# hw-demo01.net
KiCad netlist of a schematic drawn in EAGLE
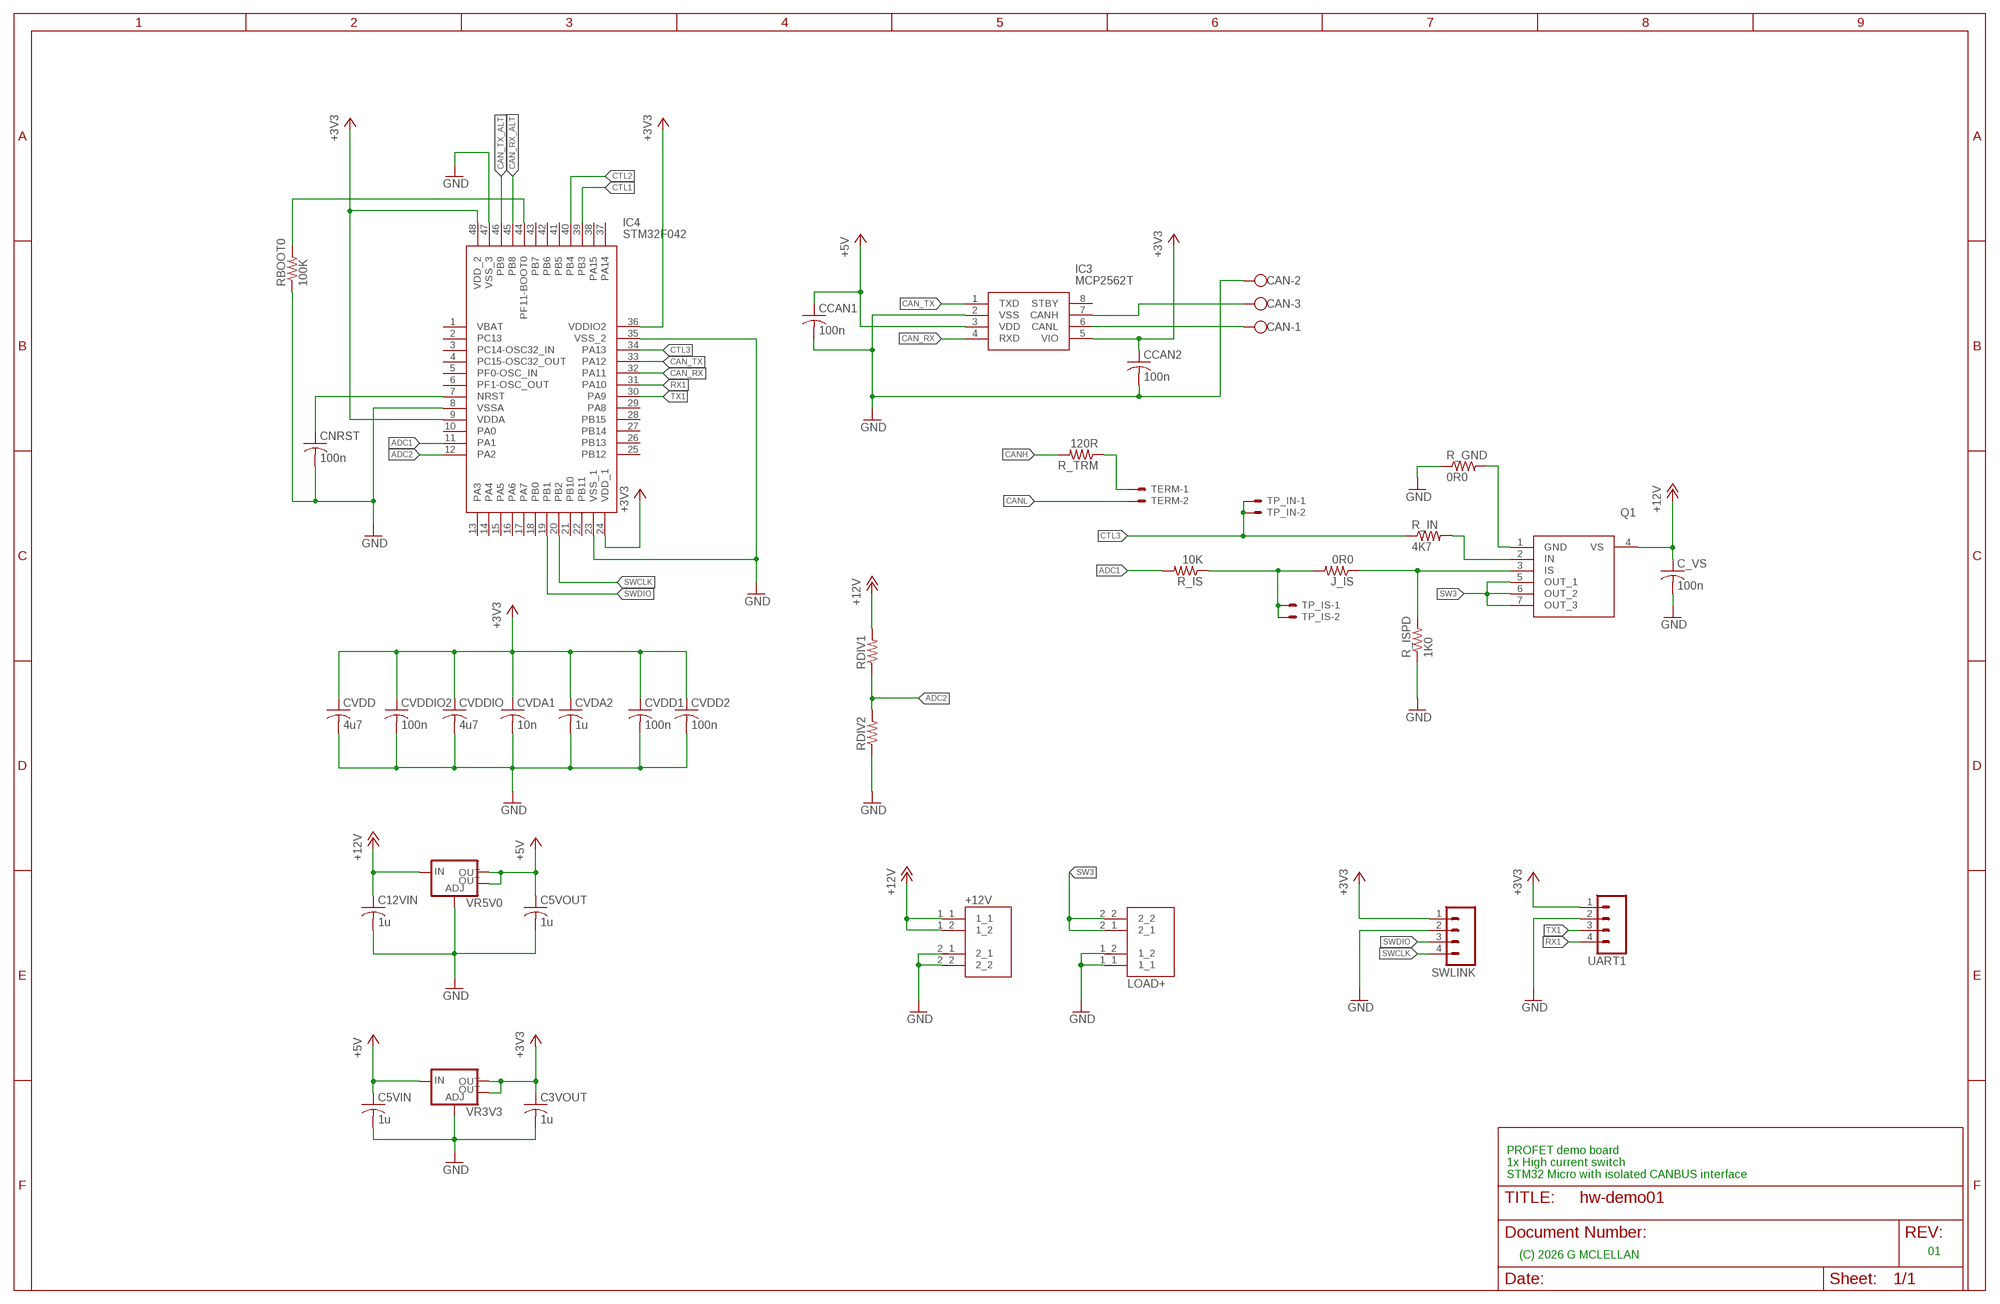
[diagram p0: schematic, sheet 1]

(export (version "E")
  (design (tool "Eeschema 10.0.6"))
  (components
    (comp (ref "+12V")
      (value "VP0265840000G")
      (footprint "eagle-import:AMPHENOL_VP0265840000G")
      (fields (field (name "MANUFACTURER") "Amphenol Anytek"))
      (libsource (lib "eagle-import") (part "VP0265840000G"))
    )
    (comp (ref "C3VOUT")
      (value "1u")
      (footprint "eagle-import:C0805K")
      (libsource (lib "eagle-import") (part "C-USC0805K"))
    )
    (comp (ref "C5VIN")
      (value "1u")
      (footprint "eagle-import:C1206K")
      (libsource (lib "eagle-import") (part "C-USC1206K"))
    )
    (comp (ref "C5VOUT")
      (value "1u")
      (footprint "eagle-import:C0805K")
      (libsource (lib "eagle-import") (part "C-USC0805K"))
    )
    (comp (ref "C12VIN")
      (value "1u")
      (footprint "eagle-import:C1206K")
      (libsource (lib "eagle-import") (part "C-USC1206K"))
    )
    (comp (ref "CAN")
      (value "W237-103")
      (footprint "eagle-import:W237-103")
      (fields (field (name "MPN") "237-103"))
      (libsource (lib "eagle-import") (part "W237-103"))
    )
    (comp (ref "CCAN1")
      (value "100n")
      (footprint "eagle-import:C0603K")
      (libsource (lib "eagle-import") (part "C-USC0603K"))
    )
    (comp (ref "CCAN2")
      (value "100n")
      (footprint "eagle-import:C0603K")
      (libsource (lib "eagle-import") (part "C-USC0603K"))
    )
    (comp (ref "CNRST")
      (value "100n")
      (footprint "eagle-import:C0603K")
      (libsource (lib "eagle-import") (part "C-USC0603K"))
    )
    (comp (ref "CVDA1")
      (value "10n")
      (footprint "eagle-import:C0603K")
      (libsource (lib "eagle-import") (part "C-USC0603K"))
    )
    (comp (ref "CVDA2")
      (value "1u")
      (footprint "eagle-import:C0603K")
      (libsource (lib "eagle-import") (part "C-USC0603K"))
    )
    (comp (ref "CVDD")
      (value "4u7")
      (footprint "eagle-import:C0603K")
      (libsource (lib "eagle-import") (part "C-USC0603K"))
    )
    (comp (ref "CVDD1")
      (value "100n")
      (footprint "eagle-import:C0603K")
      (libsource (lib "eagle-import") (part "C-USC0603K"))
    )
    (comp (ref "CVDD2")
      (value "100n")
      (footprint "eagle-import:C0603K")
      (libsource (lib "eagle-import") (part "C-USC0603K"))
    )
    (comp (ref "CVDDIO")
      (value "4u7")
      (footprint "eagle-import:C0603K")
      (libsource (lib "eagle-import") (part "C-USC0603K"))
    )
    (comp (ref "CVDDIO2")
      (value "100n")
      (footprint "eagle-import:C0603K")
      (libsource (lib "eagle-import") (part "C-USC0603K"))
    )
    (comp (ref "C_VS")
      (value "100n")
      (footprint "eagle-import:C0603K")
      (libsource (lib "eagle-import") (part "C-USC0603K"))
    )
    (comp (ref "IC3")
      (value "MCP2562T")
      (footprint "eagle-import:SOIC127P600X175-8N")
      (fields
        (field (name "MANUFACTURER_PART_NUMBER") "MCP2562T-H/SN")
        (field (name "MOUSER_PART_NUMBER") "579-MCP2562T-H/SN")
      )
      (libsource (lib "eagle-import") (part "MCP2562T-H_SN"))
    )
    (comp (ref "IC4")
      (value "STM32F042")
      (footprint "eagle-import:QFP50P900X900X160-48N")
      (fields
        (field (name "MANUFACTURER_PART_NUMBER") "STM32F042C6T7")
        (field (name "MOUSER_PART_NUMBER") "511-STM32F042C6T7")
      )
      (libsource (lib "eagle-import") (part "STM32F042C6T7"))
    )
    (comp (ref "J_IS")
      (value "0R0")
      (footprint "eagle-import:0207_12")
      (libsource (lib "eagle-import") (part "R-US_0207/12"))
    )
    (comp (ref "LOAD+")
      (value "VP0265840000G")
      (footprint "eagle-import:AMPHENOL_VP0265840000G")
      (fields (field (name "MANUFACTURER") "Amphenol Anytek"))
      (libsource (lib "eagle-import") (part "VP0265840000G"))
    )
    (comp (ref "Q1")
      (value "BTS500101TADATMA2")
      (footprint "eagle-import:BTS500101TADATMA2")
      (fields (field (name "MOUSER_PART_NUMBER") "726-BTS500101TADATM2"))
      (libsource (lib "eagle-import") (part "BTS500101TADATMA2"))
    )
    (comp (ref "RBOOT0")
      (value "100K")
      (footprint "eagle-import:R0603")
      (libsource (lib "eagle-import") (part "R-US_R0603"))
    )
    (comp (ref "RDIV1")
      (value "R-US_R0805")
      (footprint "eagle-import:R0805")
      (libsource (lib "eagle-import") (part "R-US_R0805"))
    )
    (comp (ref "RDIV2")
      (value "R-US_R0805")
      (footprint "eagle-import:R0805")
      (libsource (lib "eagle-import") (part "R-US_R0805"))
    )
    (comp (ref "R_GND")
      (value "0R0")
      (footprint "eagle-import:R1206W")
      (libsource (lib "eagle-import") (part "R-US_R1206W"))
    )
    (comp (ref "R_IN")
      (value "4K7")
      (footprint "eagle-import:0207_12")
      (libsource (lib "eagle-import") (part "R-US_0207/12"))
    )
    (comp (ref "R_IS")
      (value "10K")
      (footprint "eagle-import:0207_12")
      (libsource (lib "eagle-import") (part "R-US_0207/12"))
    )
    (comp (ref "R_ISPD")
      (value "1K0")
      (footprint "eagle-import:0207_12")
      (libsource (lib "eagle-import") (part "R-US_0207/12"))
    )
    (comp (ref "R_TRM")
      (value "120R")
      (footprint "eagle-import:0204_7")
      (libsource (lib "eagle-import") (part "R-US_0204/7"))
    )
    (comp (ref "SWLINK")
      (value "M04LOCK")
      (footprint "eagle-import:1X04_LOCK")
      (libsource (lib "eagle-import") (part "M04LOCK"))
    )
    (comp (ref "TERM")
      (value "22-23-2021")
      (footprint "eagle-import:22-23-2021")
      (fields (field (name "MF") "MOLEX"))
      (libsource (lib "eagle-import") (part "22-23-2021"))
    )
    (comp (ref "TP_IN")
      (value "22-23-2021")
      (footprint "eagle-import:22-23-2021")
      (fields (field (name "MF") "MOLEX"))
      (libsource (lib "eagle-import") (part "22-23-2021"))
    )
    (comp (ref "TP_IS")
      (value "22-23-2021")
      (footprint "eagle-import:22-23-2021")
      (fields (field (name "MF") "MOLEX"))
      (libsource (lib "eagle-import") (part "22-23-2021"))
    )
    (comp (ref "UART1")
      (value "M04LOCK")
      (footprint "eagle-import:1X04_LOCK")
      (libsource (lib "eagle-import") (part "M04LOCK"))
    )
    (comp (ref "VR3V3")
      (value "V_REG_LM1117SOT223")
      (footprint "eagle-import:SOT223")
      (libsource (lib "eagle-import") (part "V_REG_LM1117SOT223"))
    )
    (comp (ref "VR5V0")
      (value "V_REG_LM1117SOT223")
      (footprint "eagle-import:SOT223")
      (libsource (lib "eagle-import") (part "V_REG_LM1117SOT223"))
    )
  )
  (nets
    (net (code "1") (name "+3V3") (class "Default")
      (node (ref "C3VOUT") (pin "1") (pinfunction "1_1") (pintype "passive"))
      (node (ref "CCAN2") (pin "1") (pinfunction "1_1") (pintype "passive"))
      (node (ref "CVDA1") (pin "1") (pinfunction "1_1") (pintype "passive"))
      (node (ref "CVDA2") (pin "1") (pinfunction "1_1") (pintype "passive"))
      (node (ref "CVDD") (pin "1") (pinfunction "1_1") (pintype "passive"))
      (node (ref "CVDD1") (pin "1") (pinfunction "1_1") (pintype "passive"))
      (node (ref "CVDD2") (pin "1") (pinfunction "1_1") (pintype "passive"))
      (node (ref "CVDDIO") (pin "1") (pinfunction "1_1") (pintype "passive"))
      (node (ref "CVDDIO2") (pin "1") (pinfunction "1_1") (pintype "passive"))
      (node (ref "IC3") (pin "5") (pinfunction "VIO_5") (pintype "bidirectional"))
      (node (ref "IC4") (pin "24") (pinfunction "VDD_1_24") (pintype "bidirectional"))
      (node (ref "IC4") (pin "36") (pinfunction "VDDIO2_36") (pintype "bidirectional"))
      (node (ref "IC4") (pin "48") (pinfunction "VDD_2_48") (pintype "bidirectional"))
      (node (ref "IC4") (pin "9") (pinfunction "VDDA_9") (pintype "bidirectional"))
      (node (ref "SWLINK") (pin "1") (pinfunction "1_1") (pintype "passive"))
      (node (ref "UART1") (pin "1") (pinfunction "1_1") (pintype "passive"))
      (node (ref "VR3V3") (pin "2") (pinfunction "OUT_2") (pintype "output"))
      (node (ref "VR3V3") (pin "4") (pinfunction "OUT_4") (pintype "output"))
    )
    (net (code "2") (name "+5V") (class "Default")
      (node (ref "C5VIN") (pin "1") (pinfunction "1_1") (pintype "passive"))
      (node (ref "C5VOUT") (pin "1") (pinfunction "1_1") (pintype "passive"))
      (node (ref "CCAN1") (pin "1") (pinfunction "1_1") (pintype "passive"))
      (node (ref "IC3") (pin "3") (pinfunction "VDD_3") (pintype "bidirectional"))
      (node (ref "VR3V3") (pin "3") (pinfunction "IN_3") (pintype "input"))
      (node (ref "VR5V0") (pin "2") (pinfunction "OUT_2") (pintype "output"))
      (node (ref "VR5V0") (pin "4") (pinfunction "OUT_4") (pintype "output"))
    )
    (net (code "3") (name "+12V") (class "Default")
      (node (ref "+12V") (pin "1_1") (pinfunction "1_1_1_1") (pintype "passive"))
      (node (ref "+12V") (pin "1_2") (pinfunction "1_2_1_2") (pintype "passive"))
      (node (ref "C12VIN") (pin "1") (pinfunction "1_1") (pintype "passive"))
      (node (ref "C_VS") (pin "1") (pinfunction "1_1") (pintype "passive"))
      (node (ref "Q1") (pin "4") (pinfunction "VS_4") (pintype "bidirectional"))
      (node (ref "RDIV1") (pin "2") (pinfunction "2_2") (pintype "passive"))
      (node (ref "VR5V0") (pin "3") (pinfunction "IN_3") (pintype "input"))
    )
    (net (code "4") (name "ADC1") (class "Default")
      (node (ref "IC4") (pin "11") (pinfunction "PA1_11") (pintype "bidirectional"))
      (node (ref "R_IS") (pin "2") (pinfunction "2_2") (pintype "passive"))
    )
    (net (code "5") (name "ADC2") (class "Default")
      (node (ref "IC4") (pin "12") (pinfunction "PA2_12") (pintype "bidirectional"))
      (node (ref "RDIV1") (pin "1") (pinfunction "1_1") (pintype "passive"))
      (node (ref "RDIV2") (pin "2") (pinfunction "2_2") (pintype "passive"))
    )
    (net (code "6") (name "CANH") (class "Default")
      (node (ref "CAN") (pin "3") (pinfunction "KL_3") (pintype "passive"))
      (node (ref "IC3") (pin "7") (pinfunction "CANH_7") (pintype "bidirectional"))
      (node (ref "R_TRM") (pin "2") (pinfunction "2_2") (pintype "passive"))
    )
    (net (code "7") (name "CANL") (class "Default")
      (node (ref "CAN") (pin "1") (pinfunction "KL_1") (pintype "passive"))
      (node (ref "IC3") (pin "6") (pinfunction "CANL_6") (pintype "bidirectional"))
      (node (ref "TERM") (pin "2") (pinfunction "S_2") (pintype "passive"))
    )
    (net (code "8") (name "CAN_RX") (class "Default")
      (node (ref "IC3") (pin "4") (pinfunction "RXD_4") (pintype "bidirectional"))
      (node (ref "IC4") (pin "32") (pinfunction "PA11_32") (pintype "bidirectional"))
    )
    (net (code "9") (name "CAN_RX_ALT") (class "Default")
      (node (ref "IC4") (pin "45") (pinfunction "PB8_45") (pintype "bidirectional"))
    )
    (net (code "10") (name "CAN_TX") (class "Default")
      (node (ref "IC3") (pin "1") (pinfunction "TXD_1") (pintype "bidirectional"))
      (node (ref "IC4") (pin "33") (pinfunction "PA12_33") (pintype "bidirectional"))
    )
    (net (code "11") (name "CAN_TX_ALT") (class "Default")
      (node (ref "IC4") (pin "46") (pinfunction "PB9_46") (pintype "bidirectional"))
    )
    (net (code "12") (name "CTL1") (class "Default")
      (node (ref "IC4") (pin "39") (pinfunction "PB3_39") (pintype "bidirectional"))
    )
    (net (code "13") (name "CTL2") (class "Default")
      (node (ref "IC4") (pin "40") (pinfunction "PB4_40") (pintype "bidirectional"))
    )
    (net (code "14") (name "CTL3") (class "Default")
      (node (ref "IC4") (pin "34") (pinfunction "PA13_34") (pintype "bidirectional"))
      (node (ref "R_IN") (pin "1") (pinfunction "1_1") (pintype "passive"))
      (node (ref "TP_IN") (pin "1") (pinfunction "S_1") (pintype "passive"))
      (node (ref "TP_IN") (pin "2") (pinfunction "S_2") (pintype "passive"))
    )
    (net (code "15") (name "GND") (class "Default")
      (node (ref "+12V") (pin "2_1") (pinfunction "2_1_2_1") (pintype "passive"))
      (node (ref "+12V") (pin "2_2") (pinfunction "2_2_2_2") (pintype "passive"))
      (node (ref "C12VIN") (pin "2") (pinfunction "2_2") (pintype "passive"))
      (node (ref "C3VOUT") (pin "2") (pinfunction "2_2") (pintype "passive"))
      (node (ref "C5VIN") (pin "2") (pinfunction "2_2") (pintype "passive"))
      (node (ref "C5VOUT") (pin "2") (pinfunction "2_2") (pintype "passive"))
      (node (ref "CAN") (pin "2") (pinfunction "KL_2") (pintype "passive"))
      (node (ref "CCAN1") (pin "2") (pinfunction "2_2") (pintype "passive"))
      (node (ref "CCAN2") (pin "2") (pinfunction "2_2") (pintype "passive"))
      (node (ref "CNRST") (pin "2") (pinfunction "2_2") (pintype "passive"))
      (node (ref "CVDA1") (pin "2") (pinfunction "2_2") (pintype "passive"))
      (node (ref "CVDA2") (pin "2") (pinfunction "2_2") (pintype "passive"))
      (node (ref "CVDD") (pin "2") (pinfunction "2_2") (pintype "passive"))
      (node (ref "CVDD1") (pin "2") (pinfunction "2_2") (pintype "passive"))
      (node (ref "CVDD2") (pin "2") (pinfunction "2_2") (pintype "passive"))
      (node (ref "CVDDIO") (pin "2") (pinfunction "2_2") (pintype "passive"))
      (node (ref "CVDDIO2") (pin "2") (pinfunction "2_2") (pintype "passive"))
      (node (ref "C_VS") (pin "2") (pinfunction "2_2") (pintype "passive"))
      (node (ref "IC3") (pin "2") (pinfunction "VSS_2") (pintype "bidirectional"))
      (node (ref "IC4") (pin "23") (pinfunction "VSS_1_23") (pintype "bidirectional"))
      (node (ref "IC4") (pin "35") (pinfunction "VSS_2_35") (pintype "bidirectional"))
      (node (ref "IC4") (pin "47") (pinfunction "VSS_3_47") (pintype "bidirectional"))
      (node (ref "IC4") (pin "8") (pinfunction "VSSA_8") (pintype "bidirectional"))
      (node (ref "LOAD+") (pin "1_1") (pinfunction "1_1_1_1") (pintype "passive"))
      (node (ref "LOAD+") (pin "1_2") (pinfunction "1_2_1_2") (pintype "passive"))
      (node (ref "RBOOT0") (pin "1") (pinfunction "1_1") (pintype "passive"))
      (node (ref "RDIV2") (pin "1") (pinfunction "1_1") (pintype "passive"))
      (node (ref "R_GND") (pin "1") (pinfunction "1_1") (pintype "passive"))
      (node (ref "R_ISPD") (pin "1") (pinfunction "1_1") (pintype "passive"))
      (node (ref "SWLINK") (pin "2") (pinfunction "2_2") (pintype "passive"))
      (node (ref "UART1") (pin "2") (pinfunction "2_2") (pintype "passive"))
      (node (ref "VR3V3") (pin "1") (pinfunction "ADJ_1") (pintype "input"))
      (node (ref "VR5V0") (pin "1") (pinfunction "ADJ_1") (pintype "input"))
    )
    (net (code "16") (name "Net-(IC4-NRST)") (class "Default")
      (node (ref "CNRST") (pin "1") (pinfunction "1_1") (pintype "passive"))
      (node (ref "IC4") (pin "7") (pinfunction "NRST_7") (pintype "bidirectional"))
    )
    (net (code "17") (name "Net-(IC4-PF11-BOOT0)") (class "Default")
      (node (ref "IC4") (pin "44") (pinfunction "PF11-BOOT0_44") (pintype "bidirectional"))
      (node (ref "RBOOT0") (pin "2") (pinfunction "2_2") (pintype "passive"))
    )
    (net (code "18") (name "Net-(Q1-GND)") (class "Default")
      (node (ref "Q1") (pin "1") (pinfunction "GND_1") (pintype "bidirectional"))
      (node (ref "R_GND") (pin "2") (pinfunction "2_2") (pintype "passive"))
    )
    (net (code "19") (name "Net-(Q1-IN)") (class "Default")
      (node (ref "Q1") (pin "2") (pinfunction "IN_2") (pintype "bidirectional"))
      (node (ref "R_IN") (pin "2") (pinfunction "2_2") (pintype "passive"))
    )
    (net (code "20") (name "Net-(Q1-IS)") (class "Default")
      (node (ref "J_IS") (pin "1") (pinfunction "1_1") (pintype "passive"))
      (node (ref "Q1") (pin "3") (pinfunction "IS_3") (pintype "bidirectional"))
      (node (ref "R_ISPD") (pin "2") (pinfunction "2_2") (pintype "passive"))
    )
    (net (code "21") (name "Net-(TERMA-S)") (class "Default")
      (node (ref "R_TRM") (pin "1") (pinfunction "1_1") (pintype "passive"))
      (node (ref "TERM") (pin "1") (pinfunction "S_1") (pintype "passive"))
    )
    (net (code "22") (name "Net-(TP_ISA-S)") (class "Default")
      (node (ref "J_IS") (pin "2") (pinfunction "2_2") (pintype "passive"))
      (node (ref "R_IS") (pin "1") (pinfunction "1_1") (pintype "passive"))
      (node (ref "TP_IS") (pin "1") (pinfunction "S_1") (pintype "passive"))
      (node (ref "TP_IS") (pin "2") (pinfunction "S_2") (pintype "passive"))
    )
    (net (code "23") (name "RX1") (class "Default")
      (node (ref "IC4") (pin "31") (pinfunction "PA10_31") (pintype "bidirectional"))
      (node (ref "UART1") (pin "4") (pinfunction "4_4") (pintype "passive"))
    )
    (net (code "24") (name "SW3") (class "Default")
      (node (ref "LOAD+") (pin "2_1") (pinfunction "2_1_2_1") (pintype "passive"))
      (node (ref "LOAD+") (pin "2_2") (pinfunction "2_2_2_2") (pintype "passive"))
      (node (ref "Q1") (pin "5") (pinfunction "OUT_1_5") (pintype "bidirectional"))
      (node (ref "Q1") (pin "6") (pinfunction "OUT_2_6") (pintype "bidirectional"))
      (node (ref "Q1") (pin "7") (pinfunction "OUT_3_7") (pintype "bidirectional"))
    )
    (net (code "25") (name "SWCLK") (class "Default")
      (node (ref "IC4") (pin "20") (pinfunction "PB2_20") (pintype "bidirectional"))
      (node (ref "SWLINK") (pin "4") (pinfunction "4_4") (pintype "passive"))
    )
    (net (code "26") (name "SWDIO") (class "Default")
      (node (ref "IC4") (pin "19") (pinfunction "PB1_19") (pintype "bidirectional"))
      (node (ref "SWLINK") (pin "3") (pinfunction "3_3") (pintype "passive"))
    )
    (net (code "27") (name "TX1") (class "Default")
      (node (ref "IC4") (pin "30") (pinfunction "PA9_30") (pintype "bidirectional"))
      (node (ref "UART1") (pin "3") (pinfunction "3_3") (pintype "passive"))
    )
    (net (code "28") (name "unconnected-(IC3-STBY-Pad8)") (class "Default")
      (node (ref "IC3") (pin "8") (pinfunction "STBY_8") (pintype "bidirectional"))
    )
    (net (code "29") (name "unconnected-(IC4-PA0-Pad10)") (class "Default")
      (node (ref "IC4") (pin "10") (pinfunction "PA0_10") (pintype "bidirectional"))
    )
    (net (code "30") (name "unconnected-(IC4-PA3-Pad13)") (class "Default")
      (node (ref "IC4") (pin "13") (pinfunction "PA3_13") (pintype "bidirectional"))
    )
    (net (code "31") (name "unconnected-(IC4-PA4-Pad14)") (class "Default")
      (node (ref "IC4") (pin "14") (pinfunction "PA4_14") (pintype "bidirectional"))
    )
    (net (code "32") (name "unconnected-(IC4-PA5-Pad15)") (class "Default")
      (node (ref "IC4") (pin "15") (pinfunction "PA5_15") (pintype "bidirectional"))
    )
    (net (code "33") (name "unconnected-(IC4-PA6-Pad16)") (class "Default")
      (node (ref "IC4") (pin "16") (pinfunction "PA6_16") (pintype "bidirectional"))
    )
    (net (code "34") (name "unconnected-(IC4-PA7-Pad17)") (class "Default")
      (node (ref "IC4") (pin "17") (pinfunction "PA7_17") (pintype "bidirectional"))
    )
    (net (code "35") (name "unconnected-(IC4-PA8-Pad29)") (class "Default")
      (node (ref "IC4") (pin "29") (pinfunction "PA8_29") (pintype "bidirectional"))
    )
    (net (code "36") (name "unconnected-(IC4-PA14-Pad37)") (class "Default")
      (node (ref "IC4") (pin "37") (pinfunction "PA14_37") (pintype "bidirectional"))
    )
    (net (code "37") (name "unconnected-(IC4-PA15-Pad38)") (class "Default")
      (node (ref "IC4") (pin "38") (pinfunction "PA15_38") (pintype "bidirectional"))
    )
    (net (code "38") (name "unconnected-(IC4-PB0-Pad18)") (class "Default")
      (node (ref "IC4") (pin "18") (pinfunction "PB0_18") (pintype "bidirectional"))
    )
    (net (code "39") (name "unconnected-(IC4-PB5-Pad41)") (class "Default")
      (node (ref "IC4") (pin "41") (pinfunction "PB5_41") (pintype "bidirectional"))
    )
    (net (code "40") (name "unconnected-(IC4-PB6-Pad42)") (class "Default")
      (node (ref "IC4") (pin "42") (pinfunction "PB6_42") (pintype "bidirectional"))
    )
    (net (code "41") (name "unconnected-(IC4-PB7-Pad43)") (class "Default")
      (node (ref "IC4") (pin "43") (pinfunction "PB7_43") (pintype "bidirectional"))
    )
    (net (code "42") (name "unconnected-(IC4-PB10-Pad21)") (class "Default")
      (node (ref "IC4") (pin "21") (pinfunction "PB10_21") (pintype "bidirectional"))
    )
    (net (code "43") (name "unconnected-(IC4-PB11-Pad22)") (class "Default")
      (node (ref "IC4") (pin "22") (pinfunction "PB11_22") (pintype "bidirectional"))
    )
    (net (code "44") (name "unconnected-(IC4-PB12-Pad25)") (class "Default")
      (node (ref "IC4") (pin "25") (pinfunction "PB12_25") (pintype "bidirectional"))
    )
    (net (code "45") (name "unconnected-(IC4-PB13-Pad26)") (class "Default")
      (node (ref "IC4") (pin "26") (pinfunction "PB13_26") (pintype "bidirectional"))
    )
    (net (code "46") (name "unconnected-(IC4-PB14-Pad27)") (class "Default")
      (node (ref "IC4") (pin "27") (pinfunction "PB14_27") (pintype "bidirectional"))
    )
    (net (code "47") (name "unconnected-(IC4-PB15-Pad28)") (class "Default")
      (node (ref "IC4") (pin "28") (pinfunction "PB15_28") (pintype "bidirectional"))
    )
    (net (code "48") (name "unconnected-(IC4-PC13-Pad2)") (class "Default")
      (node (ref "IC4") (pin "2") (pinfunction "PC13_2") (pintype "bidirectional"))
    )
    (net (code "49") (name "unconnected-(IC4-PC14-OSC32_IN-Pad3)") (class "Default")
      (node (ref "IC4") (pin "3") (pinfunction "PC14-OSC32_IN_3") (pintype "bidirectional"))
    )
    (net (code "50") (name "unconnected-(IC4-PC15-OSC32_OUT-Pad4)") (class "Default")
      (node (ref "IC4") (pin "4") (pinfunction "PC15-OSC32_OUT_4") (pintype "bidirectional"))
    )
    (net (code "51") (name "unconnected-(IC4-PF0-OSC_IN-Pad5)") (class "Default")
      (node (ref "IC4") (pin "5") (pinfunction "PF0-OSC_IN_5") (pintype "bidirectional"))
    )
    (net (code "52") (name "unconnected-(IC4-PF1-OSC_OUT-Pad6)") (class "Default")
      (node (ref "IC4") (pin "6") (pinfunction "PF1-OSC_OUT_6") (pintype "bidirectional"))
    )
    (net (code "53") (name "unconnected-(IC4-VBAT-Pad1)") (class "Default")
      (node (ref "IC4") (pin "1") (pinfunction "VBAT_1") (pintype "bidirectional"))
    )
  )
)
